# Audio-Amplifier.net
KiCad netlist of a schematic drawn in Altium Designer
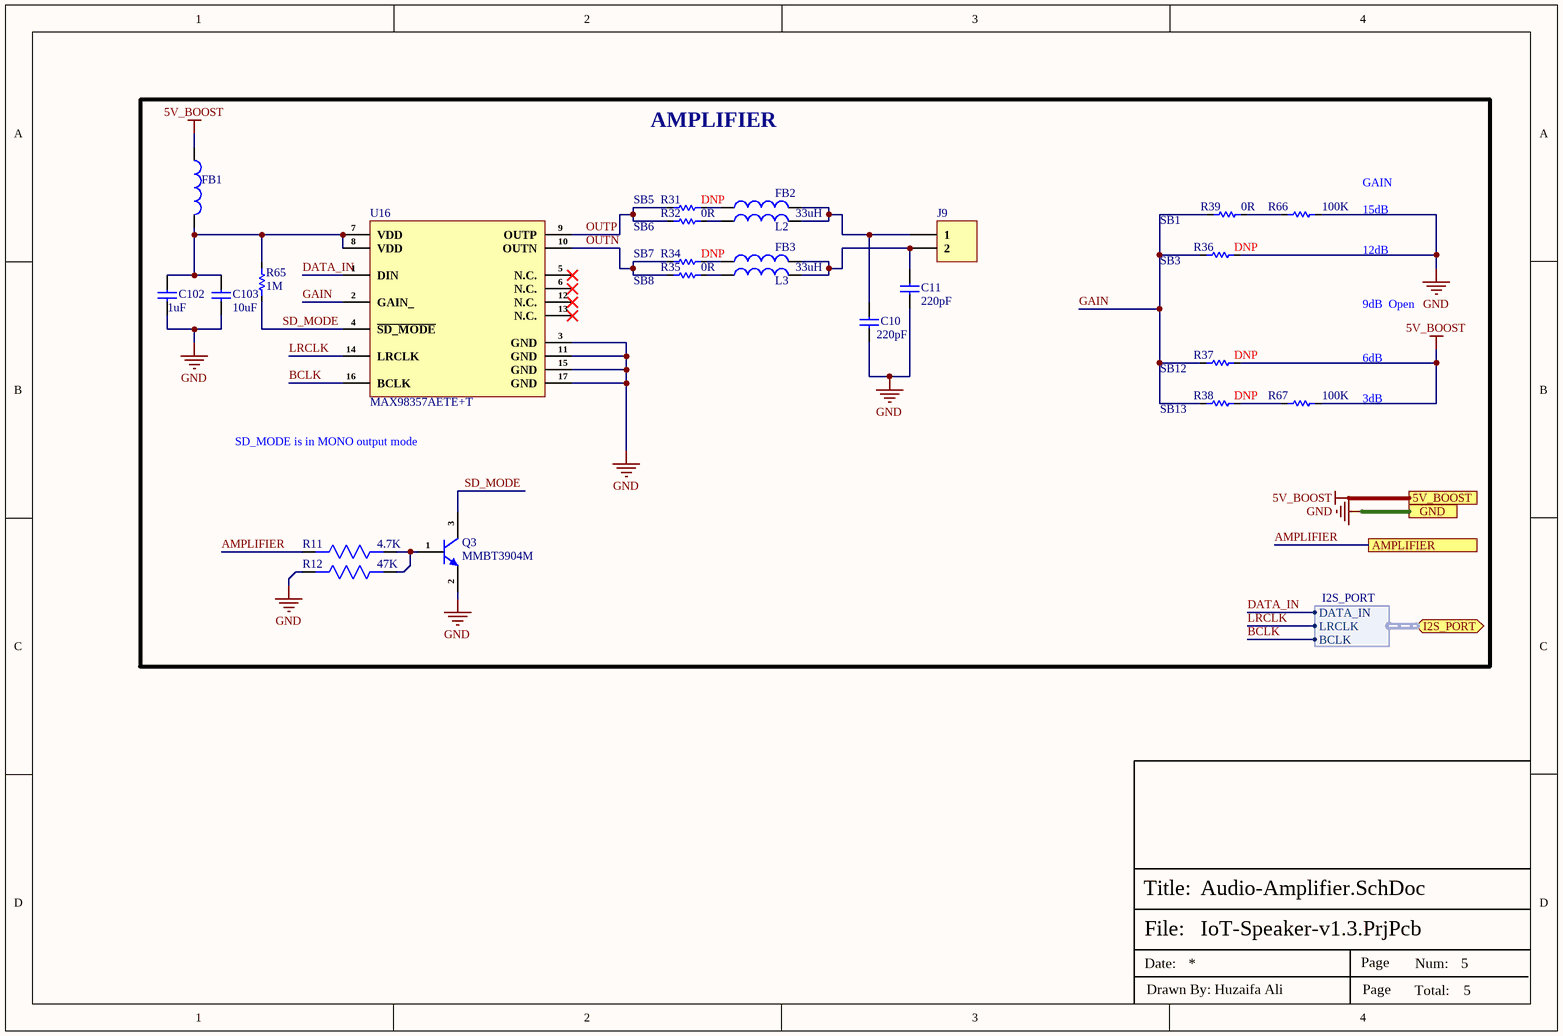
[diagram p0: Audio-Amplifier.SchDoc]

(export (version "E")
  (design (tool "Eeschema 10.0.6"))
  (components
    (comp (ref "C10")
      (value "220pF")
      (footprint "Cap-0402")
      (description "CAP CER 220PF 50V C0G/NPO 0402")
      (fields
        (field (name "MANUFACTURER") "Yageo")
        (field (name "MANUFACTURER PART NUMBER") "CC0402JRNPO9BN221")
      )
      (libsource (lib "eSpark_centralized_Library(2022)") (part "CC0402JRNPO9BN221"))
    )
    (comp (ref "C11")
      (value "220pF")
      (footprint "Cap-0402")
      (description "CAP CER 220PF 50V C0G/NPO 0402")
      (fields
        (field (name "MANUFACTURER") "Yageo")
        (field (name "MANUFACTURER PART NUMBER") "CC0402JRNPO9BN221")
      )
      (libsource (lib "eSpark_centralized_Library(2022)") (part "CC0402JRNPO9BN221"))
    )
    (comp (ref "C102")
      (value "1uF")
      (footprint "Cap-0603")
      (description "CAP CER 1UF 25V X5R 0603")
      (fields
        (field (name "MANUFACTURER") "Yageo")
        (field (name "MANUFACTURER PART NUMBER") "CC0603KRX5R8BB105")
      )
      (libsource (lib "eSpark_centralized_Library(2022)") (part "CC0603KRX5R8BB105"))
    )
    (comp (ref "C103")
      (value "10uF")
      (footprint "Cap-0805")
      (description "CAP CER 10UF 25V X5R 0805")
      (fields
        (field (name "MANUFACTURER") "Yageo")
        (field (name "MANUFACTURER PART NUMBER") "CC0805KKX5R8BB106")
      )
      (libsource (lib "eSpark_centralized_Library(2022)") (part "CC0805KKX5R8BB106"))
    )
    (comp (ref "FB1")
      (value "BLM18PG300SN1D")
      (footprint "IND-0603 (1608 Metric)")
      (description "FERRITE BEAD 30 OHM 0603 1LN / Ferrite Beads Multi-Layer 30Ohm 100MHz 1A 0.05Ohm DCR 0603 T/R")
      (fields (field (name "MANUFACTURER") "Murata") (field (name "TOLERANCE") "25%"))
      (libsource (lib "eSpark_centralized_Library(2022)") (part "BLM18PG300SN1D"))
    )
    (comp (ref "FB2")
      (value "BLM18PG300SN1D")
      (footprint "IND-0603 (1608 Metric)")
      (description "FERRITE BEAD 30 OHM 0603 1LN / Ferrite Beads Multi-Layer 30Ohm 100MHz 1A 0.05Ohm DCR 0603 T/R")
      (fields (field (name "MANUFACTURER") "Murata") (field (name "TOLERANCE") "25%"))
      (libsource (lib "eSpark_centralized_Library(2022)") (part "BLM18PG300SN1D"))
    )
    (comp (ref "FB3")
      (value "BLM18PG300SN1D")
      (footprint "IND-0603 (1608 Metric)")
      (description "FERRITE BEAD 30 OHM 0603 1LN / Ferrite Beads Multi-Layer 30Ohm 100MHz 1A 0.05Ohm DCR 0603 T/R")
      (fields (field (name "MANUFACTURER") "Murata") (field (name "TOLERANCE") "25%"))
      (libsource (lib "eSpark_centralized_Library(2022)") (part "BLM18PG300SN1D"))
    )
    (comp (ref "J9")
      (value "61300211121")
      (footprint "HDR1X2_")
      (description "CONN HEADER VERT 2POS 2.54MM")
      (fields (field (name "MANUFACTURER") "Wurth Electronics"))
      (libsource (lib "eSpark_centralized_Library(2022)") (part "61300211121"))
    )
    (comp (ref "L2")
      (value "33uH")
      (footprint "VLCF5024T-330MR50-2")
      (description "FIXED IND 33UH 500MA 275MOHM SMD")
      (fields
        (field (name "MANUFACTURER") "TDK")
        (field (name "MANUFACTURER PART NUMBER") "VLCF5024T-330MR50-2")
      )
      (libsource (lib "eSpark_centralized_Library(2022)") (part "VLCF5024T-330MR50-2"))
    )
    (comp (ref "L3")
      (value "33uH")
      (footprint "VLCF5024T-330MR50-2")
      (description "FIXED IND 33UH 500MA 275MOHM SMD")
      (fields
        (field (name "MANUFACTURER") "TDK")
        (field (name "MANUFACTURER PART NUMBER") "VLCF5024T-330MR50-2")
      )
      (libsource (lib "eSpark_centralized_Library(2022)") (part "VLCF5024T-330MR50-2"))
    )
    (comp (ref "Q3")
      (value "MMBT3904M")
      (footprint "SOT-723")
      (fields (field (name "MANUFACTURER") "TECH PUBLIC") (field (name "LCSC PART NUMBER") "C2923360"))
      (libsource (lib "eSpark_centralized_Library(2022)") (part "MMBT3904M"))
    )
    (comp (ref "R11")
      (value "4.7K")
      (footprint "Res-0603")
      (description "RES SMD 4.7K OHM 5% 1/10W 0603")
      (fields
        (field (name "MANUFACTURER") "Yageo")
        (field (name "MANUFACTURER PART NUMBER") "RC0603JR-074K7L")
      )
      (libsource (lib "eSpark_centralized_Library(2022)") (part "RC0603JR-074K7L"))
    )
    (comp (ref "R12")
      (value "47K")
      (footprint "Res-0603")
      (description "RES 47K OHM 5% 1/10W 0603")
      (fields
        (field (name "MANUFACTURER") "Yageo")
        (field (name "MANUFACTURER PART NUMBER") "RC0603JR-0747KL")
      )
      (libsource (lib "eSpark_centralized_Library(2022)") (part "RC0603JR-0747KL"))
    )
    (comp (ref "R31")
      (value "DNP")
      (footprint "Res-0603")
      (description "RES SMD 0R, 1%, 0.1W, 0603")
      (fields
        (field (name "MANUFACTURER") "Yageo")
        (field (name "MANUFACTURER PART NUMBER") "RC0603FR-070RL")
      )
      (libsource (lib "eSpark Libraries") (part "RC0603FR-070RL"))
    )
    (comp (ref "R32")
      (value "0R")
      (footprint "Res-0603")
      (description "RES SMD 0R, 1%, 0.1W, 0603")
      (fields
        (field (name "MANUFACTURER") "Yageo")
        (field (name "MANUFACTURER PART NUMBER") "RC0603FR-070RL")
      )
      (libsource (lib "eSpark Libraries") (part "RC0603FR-070RL"))
    )
    (comp (ref "R34")
      (value "DNP")
      (footprint "Res-0603")
      (description "RES SMD 0R, 1%, 0.1W, 0603")
      (fields
        (field (name "MANUFACTURER") "Yageo")
        (field (name "MANUFACTURER PART NUMBER") "RC0603FR-070RL")
      )
      (libsource (lib "eSpark Libraries") (part "RC0603FR-070RL"))
    )
    (comp (ref "R35")
      (value "0R")
      (footprint "Res-0603")
      (description "RES SMD 0R, 1%, 0.1W, 0603")
      (fields
        (field (name "MANUFACTURER") "Yageo")
        (field (name "MANUFACTURER PART NUMBER") "RC0603FR-070RL")
      )
      (libsource (lib "eSpark Libraries") (part "RC0603FR-070RL"))
    )
    (comp (ref "R36")
      (value "DNP")
      (footprint "Res-0603")
      (description "RES SMD 0R, 1%, 0.1W, 0603")
      (fields
        (field (name "MANUFACTURER") "Yageo")
        (field (name "MANUFACTURER PART NUMBER") "RC0603FR-070RL")
      )
      (libsource (lib "eSpark Libraries") (part "RC0603FR-070RL"))
    )
    (comp (ref "R37")
      (value "DNP")
      (footprint "Res-0603")
      (description "RES SMD 0R, 1%, 0.1W, 0603")
      (fields
        (field (name "MANUFACTURER") "Yageo")
        (field (name "MANUFACTURER PART NUMBER") "RC0603FR-070RL")
      )
      (libsource (lib "eSpark Libraries") (part "RC0603FR-070RL"))
    )
    (comp (ref "R38")
      (value "DNP")
      (footprint "Res-0603")
      (description "RES SMD 0R, 1%, 0.1W, 0603")
      (fields
        (field (name "MANUFACTURER") "Yageo")
        (field (name "MANUFACTURER PART NUMBER") "RC0603FR-070RL")
      )
      (libsource (lib "eSpark Libraries") (part "RC0603FR-070RL"))
    )
    (comp (ref "R39")
      (value "0R")
      (footprint "Res-0603")
      (description "RES SMD 0R, 1%, 0.1W, 0603")
      (fields
        (field (name "MANUFACTURER") "Yageo")
        (field (name "MANUFACTURER PART NUMBER") "RC0603FR-070RL")
      )
      (libsource (lib "eSpark Libraries") (part "RC0603FR-070RL"))
    )
    (comp (ref "R65")
      (value "1M")
      (footprint "Res-0603")
      (description "RES SMD 1M OHM 1% 1/10W 0603")
      (fields
        (field (name "MANUFACTURER") "Yageo")
        (field (name "MANUFACTURER PART NUMBER") "RC0603FR-071ML")
      )
      (libsource (lib "eSpark_centralized_Library(2022)") (part "RC0603FR-071ML"))
    )
    (comp (ref "R66")
      (value "100K")
      (footprint "Res-0603")
      (description "RES SMD 100K OHM 0.1% 1/10W 0603")
      (fields
        (field (name "MANUFACTURER") "Yageo")
        (field (name "MANUFACTURER PART NUMBER") "RT0603BRD07100KL")
      )
      (libsource (lib "eSpark_centralized_Library(2022)") (part "RT0603BRD07100KL"))
    )
    (comp (ref "R67")
      (value "100K")
      (footprint "Res-0603")
      (description "RES SMD 100K OHM 0.1% 1/10W 0603")
      (fields
        (field (name "MANUFACTURER") "Yageo")
        (field (name "MANUFACTURER PART NUMBER") "RT0603BRD07100KL")
      )
      (libsource (lib "eSpark_centralized_Library(2022)") (part "RT0603BRD07100KL"))
    )
    (comp (ref "U16")
      (value "MAX98357AETE+T")
      (footprint "TQFN-16-EP(3x3)")
      (description "Audio Amplifier, 1 Func, PQCC16")
      (fields (field (name "MANUFACTURER") "Maxim") (field (name "LCSC PART NUMBER") "C910544"))
      (libsource (lib "eSpark_centralized_Library(2022)") (part "MAX98357AETE+T"))
    )
  )
  (nets
    (net (code "2") (name "/AMPLIFIER") (class "Default") (node (ref "R11") (pin "2") (pintype "passive")))
    (net (code "3") (name "/BCLK") (class "Default")
      (node (ref "U16") (pin "16") (pinfunction "BCLK_16") (pintype "passive"))
    )
    (net (code "4") (name "/DATA_IN") (class "Default")
      (node (ref "U16") (pin "1") (pinfunction "DIN_1") (pintype "passive"))
    )
    (net (code "5") (name "/GAIN") (class "Default")
      (node (ref "R36") (pin "1") (pinfunction "1_1") (pintype "passive"))
      (node (ref "R37") (pin "1") (pinfunction "1_1") (pintype "passive"))
      (node (ref "R38") (pin "1") (pinfunction "1_1") (pintype "passive"))
      (node (ref "R39") (pin "1") (pinfunction "1_1") (pintype "passive"))
      (node (ref "U16") (pin "2") (pinfunction "GAIN__2") (pintype "passive"))
    )
    (net (code "6") (name "/LRCLK") (class "Default")
      (node (ref "U16") (pin "14") (pinfunction "LRCLK_14") (pintype "passive"))
    )
    (net (code "7") (name "/OUTN") (class "Default")
      (node (ref "R34") (pin "1") (pinfunction "1_1") (pintype "passive"))
      (node (ref "R35") (pin "1") (pinfunction "1_1") (pintype "passive"))
      (node (ref "U16") (pin "10") (pinfunction "OUTN_10") (pintype "passive"))
    )
    (net (code "8") (name "/OUTP") (class "Default")
      (node (ref "R31") (pin "1") (pinfunction "1_1") (pintype "passive"))
      (node (ref "R32") (pin "1") (pinfunction "1_1") (pintype "passive"))
      (node (ref "U16") (pin "9") (pinfunction "OUTP_9") (pintype "passive"))
    )
    (net (code "9") (name "/SD_MODE") (class "Default")
      (node (ref "Q3") (pin "3") (pinfunction "C_3") (pintype "passive"))
      (node (ref "R65") (pin "1") (pinfunction "1_1") (pintype "passive"))
      (node (ref "U16") (pin "4") (pinfunction "~{SD_MODE}_4") (pintype "passive"))
    )
    (net (code "11") (name "5V_BOOST") (class "Default")
      (node (ref "FB1") (pin "1") (pinfunction "1_1") (pintype "passive"))
      (node (ref "R37") (pin "2") (pinfunction "2_2") (pintype "passive"))
      (node (ref "R67") (pin "2") (pinfunction "2_2") (pintype "passive"))
    )
    (net (code "12") (name "GND") (class "Default")
      (node (ref "C10") (pin "1") (pinfunction "1_1") (pintype "passive"))
      (node (ref "C102") (pin "1") (pinfunction "1_1") (pintype "passive"))
      (node (ref "C103") (pin "1") (pinfunction "1_1") (pintype "passive"))
      (node (ref "C11") (pin "1") (pinfunction "1_1") (pintype "passive"))
      (node (ref "Q3") (pin "2") (pinfunction "E_2") (pintype "passive"))
      (node (ref "R12") (pin "2") (pintype "passive"))
      (node (ref "R36") (pin "2") (pinfunction "2_2") (pintype "passive"))
      (node (ref "R66") (pin "2") (pinfunction "2_2") (pintype "passive"))
      (node (ref "U16") (pin "11") (pinfunction "GND_11") (pintype "passive"))
      (node (ref "U16") (pin "15") (pinfunction "GND_15") (pintype "passive"))
      (node (ref "U16") (pin "17") (pinfunction "GND_17") (pintype "passive"))
      (node (ref "U16") (pin "3") (pinfunction "GND_3") (pintype "passive"))
    )
    (net (code "13") (name "Net-(C10-Pad2)") (class "Default")
      (node (ref "C10") (pin "2") (pinfunction "2_2") (pintype "passive"))
      (node (ref "FB2") (pin "2") (pinfunction "2_2") (pintype "passive"))
      (node (ref "J9") (pin "1") (pinfunction "1_1") (pintype "passive"))
      (node (ref "L2") (pin "2") (pinfunction "2_2") (pintype "passive"))
    )
    (net (code "14") (name "Net-(C11-Pad2)") (class "Default")
      (node (ref "C11") (pin "2") (pinfunction "2_2") (pintype "passive"))
      (node (ref "FB3") (pin "2") (pinfunction "2_2") (pintype "passive"))
      (node (ref "J9") (pin "2") (pinfunction "2_2") (pintype "passive"))
      (node (ref "L3") (pin "2") (pinfunction "2_2") (pintype "passive"))
    )
    (net (code "15") (name "Net-(C102-Pad2)") (class "Default")
      (node (ref "C102") (pin "2") (pinfunction "2_2") (pintype "passive"))
      (node (ref "C103") (pin "2") (pinfunction "2_2") (pintype "passive"))
      (node (ref "FB1") (pin "2") (pinfunction "2_2") (pintype "passive"))
      (node (ref "R65") (pin "2") (pinfunction "2_2") (pintype "passive"))
      (node (ref "U16") (pin "7") (pinfunction "VDD_7") (pintype "passive"))
      (node (ref "U16") (pin "8") (pinfunction "VDD_8") (pintype "passive"))
    )
    (net (code "16") (name "Net-(FB2-Pad1)") (class "Default")
      (node (ref "FB2") (pin "1") (pinfunction "1_1") (pintype "passive"))
      (node (ref "R31") (pin "2") (pinfunction "2_2") (pintype "passive"))
    )
    (net (code "17") (name "Net-(FB3-Pad1)") (class "Default")
      (node (ref "FB3") (pin "1") (pinfunction "1_1") (pintype "passive"))
      (node (ref "R34") (pin "2") (pinfunction "2_2") (pintype "passive"))
    )
    (net (code "18") (name "Net-(L2-Pad1)") (class "Default")
      (node (ref "L2") (pin "1") (pinfunction "1_1") (pintype "passive"))
      (node (ref "R32") (pin "2") (pinfunction "2_2") (pintype "passive"))
    )
    (net (code "19") (name "Net-(L3-Pad1)") (class "Default")
      (node (ref "L3") (pin "1") (pinfunction "1_1") (pintype "passive"))
      (node (ref "R35") (pin "2") (pinfunction "2_2") (pintype "passive"))
    )
    (net (code "20") (name "Net-(Q3-B)") (class "Default")
      (node (ref "Q3") (pin "1") (pinfunction "B_1") (pintype "passive"))
      (node (ref "R11") (pin "1") (pintype "passive"))
      (node (ref "R12") (pin "1") (pintype "passive"))
    )
    (net (code "21") (name "Net-(R38-Pad2)") (class "Default")
      (node (ref "R38") (pin "2") (pinfunction "2_2") (pintype "passive"))
      (node (ref "R67") (pin "1") (pinfunction "1_1") (pintype "passive"))
    )
    (net (code "22") (name "Net-(R39-Pad2)") (class "Default")
      (node (ref "R39") (pin "2") (pinfunction "2_2") (pintype "passive"))
      (node (ref "R66") (pin "1") (pinfunction "1_1") (pintype "passive"))
    )
    (net (code "23") (name "unconnected-(U16-N.C.-Pad5)") (class "Default")
      (node (ref "U16") (pin "5") (pinfunction "N.C._5") (pintype "passive+no_connect"))
    )
    (net (code "24") (name "unconnected-(U16-N.C.-Pad6)") (class "Default")
      (node (ref "U16") (pin "6") (pinfunction "N.C._6") (pintype "passive+no_connect"))
    )
    (net (code "25") (name "unconnected-(U16-N.C.-Pad12)") (class "Default")
      (node (ref "U16") (pin "12") (pinfunction "N.C._12") (pintype "passive+no_connect"))
    )
    (net (code "26") (name "unconnected-(U16-N.C.-Pad13)") (class "Default")
      (node (ref "U16") (pin "13") (pinfunction "N.C._13") (pintype "passive+no_connect"))
    )
  )
)
